# LCD_touch_conn.net
KiCad netlist of a schematic drawn in Altium Designer
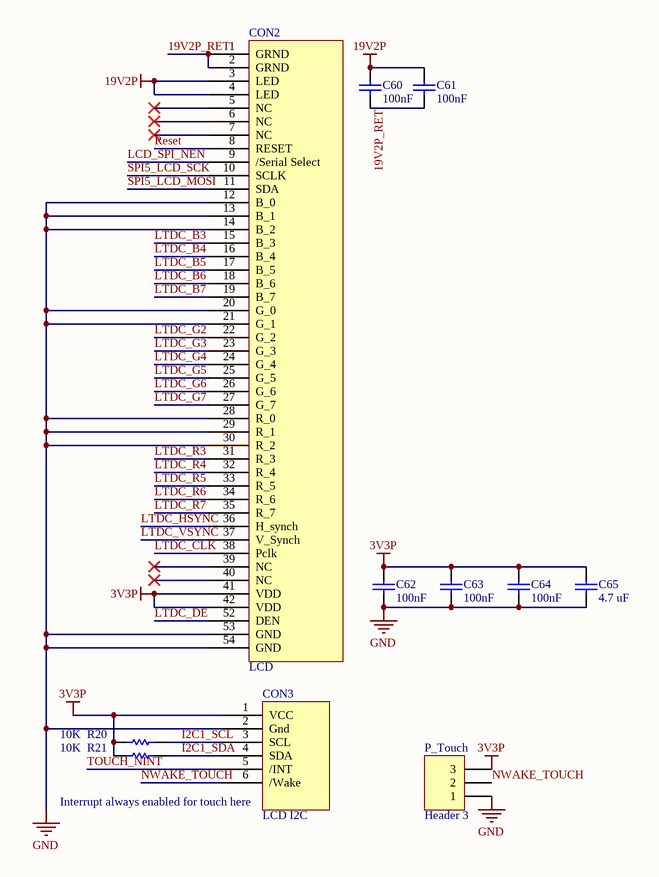
[diagram p0: LCD_touch_conn.SchDoc]

(export (version "E")
  (design (tool "Eeschema 10.0.6"))
  (components
    (comp (ref "C60")
      (value "100nF")
      (footprint "C0805")
      (description "Capacitor")
      (fields (field (name "PUBLISHER") "Altium Limited"))
      (libsource (lib "Miscellaneous Devices") (part "Cap"))
    )
    (comp (ref "C61")
      (value "100nF")
      (footprint "C0805")
      (description "Capacitor")
      (fields (field (name "PUBLISHER") "Altium Limited"))
      (libsource (lib "Miscellaneous Devices") (part "Cap"))
    )
    (comp (ref "C62")
      (value "100nF")
      (footprint "C0805")
      (description "Capacitor")
      (fields (field (name "PUBLISHER") "Altium Limited"))
      (libsource (lib "Miscellaneous Devices") (part "Cap"))
    )
    (comp (ref "C63")
      (value "100nF")
      (footprint "C0805")
      (description "Capacitor")
      (fields (field (name "PUBLISHER") "Altium Limited"))
      (libsource (lib "Miscellaneous Devices") (part "Cap"))
    )
    (comp (ref "C64")
      (value "100nF")
      (footprint "C0805")
      (description "Capacitor")
      (fields (field (name "PUBLISHER") "Altium Limited"))
      (libsource (lib "Miscellaneous Devices") (part "Cap"))
    )
    (comp (ref "C65")
      (value "4.7 uF")
      (footprint "C0805")
      (description "Capacitor")
      (fields (field (name "PUBLISHER") "Altium Limited"))
      (libsource (lib "Miscellaneous Devices") (part "Cap"))
    )
    (comp (ref "CON2")
      (value "LCD")
      (footprint "Molex54 - duplicate2")
      (libsource (lib "GameMan") (part "LCD"))
    )
    (comp (ref "CON3") (value "LCD I2C") (footprint "Molex6") (libsource (lib "GameMan") (part "LCD I2C")))
    (comp (ref "P_Touch")
      (value "Header 3")
      (footprint "HDR1X3")
      (description "Header, 3-Pin")
      (fields (field (name "PUBLISHER") "Altium Limited"))
      (libsource (lib "Miscellaneous Connectors") (part "Header 3"))
    )
    (comp (ref "R20")
      (value "10K")
      (footprint "6-0805_M")
      (description "Resistor")
      (fields (field (name "PUBLISHER") "Altium Limited"))
      (libsource (lib "Miscellaneous Devices") (part "Res1"))
    )
    (comp (ref "R21")
      (value "10K")
      (footprint "6-0805_M")
      (description "Resistor")
      (fields (field (name "PUBLISHER") "Altium Limited"))
      (libsource (lib "Miscellaneous Devices") (part "Res1"))
    )
  )
  (nets
    (net (code "1") (name "/19V2P_RET") (class "Default")
      (node (ref "C60") (pin "1") (pinfunction "1_1") (pintype "passive"))
      (node (ref "C61") (pin "1") (pinfunction "1_1") (pintype "passive"))
      (node (ref "CON2") (pin "1") (pinfunction "GRND_1") (pintype "passive"))
      (node (ref "CON2") (pin "2") (pinfunction "GRND_2") (pintype "passive"))
    )
    (net (code "2") (name "/I2C1_SCL") (class "Default")
      (node (ref "CON3") (pin "3") (pinfunction "SCL_3") (pintype "passive"))
      (node (ref "R20") (pin "2") (pinfunction "2_2") (pintype "passive"))
    )
    (net (code "3") (name "/I2C1_SDA") (class "Default")
      (node (ref "CON3") (pin "4") (pinfunction "SDA_4") (pintype "passive"))
      (node (ref "R21") (pin "2") (pinfunction "2_2") (pintype "passive"))
    )
    (net (code "4") (name "/LCD_SPI_NEN") (class "Default")
      (node (ref "CON2") (pin "9") (pinfunction "/Serial_Select_9") (pintype "passive"))
    )
    (net (code "5") (name "/LTDC_B3") (class "Default")
      (node (ref "CON2") (pin "15") (pinfunction "B_3_15") (pintype "passive"))
    )
    (net (code "6") (name "/LTDC_B4") (class "Default")
      (node (ref "CON2") (pin "16") (pinfunction "B_4_16") (pintype "passive"))
    )
    (net (code "7") (name "/LTDC_B5") (class "Default")
      (node (ref "CON2") (pin "17") (pinfunction "B_5_17") (pintype "passive"))
    )
    (net (code "8") (name "/LTDC_B6") (class "Default")
      (node (ref "CON2") (pin "18") (pinfunction "B_6_18") (pintype "passive"))
    )
    (net (code "9") (name "/LTDC_B7") (class "Default")
      (node (ref "CON2") (pin "19") (pinfunction "B_7_19") (pintype "passive"))
    )
    (net (code "10") (name "/LTDC_CLK") (class "Default")
      (node (ref "CON2") (pin "38") (pinfunction "Pclk_38") (pintype "passive"))
    )
    (net (code "11") (name "/LTDC_DE") (class "Default")
      (node (ref "CON2") (pin "52") (pinfunction "DEN_52") (pintype "passive"))
    )
    (net (code "12") (name "/LTDC_G2") (class "Default")
      (node (ref "CON2") (pin "22") (pinfunction "G_2_22") (pintype "passive"))
    )
    (net (code "13") (name "/LTDC_G3") (class "Default")
      (node (ref "CON2") (pin "23") (pinfunction "G_3_23") (pintype "passive"))
    )
    (net (code "14") (name "/LTDC_G4") (class "Default")
      (node (ref "CON2") (pin "24") (pinfunction "G_4_24") (pintype "passive"))
    )
    (net (code "15") (name "/LTDC_G5") (class "Default")
      (node (ref "CON2") (pin "25") (pinfunction "G_5_25") (pintype "passive"))
    )
    (net (code "16") (name "/LTDC_G6") (class "Default")
      (node (ref "CON2") (pin "26") (pinfunction "G_6_26") (pintype "passive"))
    )
    (net (code "17") (name "/LTDC_G7") (class "Default")
      (node (ref "CON2") (pin "27") (pinfunction "G_7_27") (pintype "passive"))
    )
    (net (code "18") (name "/LTDC_HSYNC") (class "Default")
      (node (ref "CON2") (pin "36") (pinfunction "H_synch_36") (pintype "passive"))
    )
    (net (code "19") (name "/LTDC_R3") (class "Default")
      (node (ref "CON2") (pin "31") (pinfunction "R_3_31") (pintype "passive"))
    )
    (net (code "20") (name "/LTDC_R4") (class "Default")
      (node (ref "CON2") (pin "32") (pinfunction "R_4_32") (pintype "passive"))
    )
    (net (code "21") (name "/LTDC_R5") (class "Default")
      (node (ref "CON2") (pin "33") (pinfunction "R_5_33") (pintype "passive"))
    )
    (net (code "22") (name "/LTDC_R6") (class "Default")
      (node (ref "CON2") (pin "34") (pinfunction "R_6_34") (pintype "passive"))
    )
    (net (code "23") (name "/LTDC_R7") (class "Default")
      (node (ref "CON2") (pin "35") (pinfunction "R_7_35") (pintype "passive"))
    )
    (net (code "24") (name "/LTDC_VSYNC") (class "Default")
      (node (ref "CON2") (pin "37") (pinfunction "V_Synch_37") (pintype "passive"))
    )
    (net (code "25") (name "/NWAKE_TOUCH") (class "Default")
      (node (ref "CON3") (pin "6") (pinfunction "/Wake_6") (pintype "passive"))
      (node (ref "P_Touch") (pin "2") (pinfunction "2_2") (pintype "passive"))
    )
    (net (code "26") (name "/Reset") (class "Default")
      (node (ref "CON2") (pin "8") (pinfunction "RESET_8") (pintype "passive"))
    )
    (net (code "27") (name "/SPI5_LCD_MOSI") (class "Default")
      (node (ref "CON2") (pin "11") (pinfunction "SDA_11") (pintype "passive"))
    )
    (net (code "28") (name "/SPI5_LCD_SCK") (class "Default")
      (node (ref "CON2") (pin "10") (pinfunction "SCLK_10") (pintype "passive"))
    )
    (net (code "29") (name "/TOUCH_NINT") (class "Default")
      (node (ref "CON3") (pin "5") (pinfunction "/INT_5") (pintype "passive"))
    )
    (net (code "30") (name "3V3P") (class "Default")
      (node (ref "C62") (pin "2") (pinfunction "2_2") (pintype "passive"))
      (node (ref "C63") (pin "2") (pinfunction "2_2") (pintype "passive"))
      (node (ref "C64") (pin "2") (pinfunction "2_2") (pintype "passive"))
      (node (ref "C65") (pin "2") (pinfunction "2_2") (pintype "passive"))
      (node (ref "CON2") (pin "41") (pinfunction "VDD_41") (pintype "passive"))
      (node (ref "CON2") (pin "42") (pinfunction "VDD_42") (pintype "passive"))
      (node (ref "CON3") (pin "1") (pinfunction "VCC_1") (pintype "passive"))
      (node (ref "P_Touch") (pin "3") (pinfunction "3_3") (pintype "passive"))
      (node (ref "R20") (pin "1") (pinfunction "1_1") (pintype "passive"))
      (node (ref "R21") (pin "1") (pinfunction "1_1") (pintype "passive"))
    )
    (net (code "31") (name "19V2P") (class "Default")
      (node (ref "C60") (pin "2") (pinfunction "2_2") (pintype "passive"))
      (node (ref "C61") (pin "2") (pinfunction "2_2") (pintype "passive"))
      (node (ref "CON2") (pin "3") (pinfunction "LED_3") (pintype "passive"))
      (node (ref "CON2") (pin "4") (pinfunction "LED_4") (pintype "passive"))
    )
    (net (code "32") (name "GND") (class "Default")
      (node (ref "C62") (pin "1") (pinfunction "1_1") (pintype "passive"))
      (node (ref "C63") (pin "1") (pinfunction "1_1") (pintype "passive"))
      (node (ref "C64") (pin "1") (pinfunction "1_1") (pintype "passive"))
      (node (ref "C65") (pin "1") (pinfunction "1_1") (pintype "passive"))
      (node (ref "CON2") (pin "12") (pinfunction "B_0_12") (pintype "passive"))
      (node (ref "CON2") (pin "13") (pinfunction "B_1_13") (pintype "passive"))
      (node (ref "CON2") (pin "14") (pinfunction "B_2_14") (pintype "passive"))
      (node (ref "CON2") (pin "20") (pinfunction "G_0_20") (pintype "passive"))
      (node (ref "CON2") (pin "21") (pinfunction "G_1_21") (pintype "passive"))
      (node (ref "CON2") (pin "28") (pinfunction "R_0_28") (pintype "passive"))
      (node (ref "CON2") (pin "29") (pinfunction "R_1_29") (pintype "passive"))
      (node (ref "CON2") (pin "30") (pinfunction "R_2_30") (pintype "passive"))
      (node (ref "CON2") (pin "53") (pinfunction "GND_53") (pintype "passive"))
      (node (ref "CON2") (pin "54") (pinfunction "GND_54") (pintype "passive"))
      (node (ref "CON3") (pin "2") (pinfunction "Gnd_2") (pintype "passive"))
      (node (ref "P_Touch") (pin "1") (pinfunction "1_1") (pintype "passive"))
    )
    (net (code "33") (name "unconnected-(CON2-NC-Pad5)") (class "Default")
      (node (ref "CON2") (pin "5") (pinfunction "NC_5") (pintype "passive+no_connect"))
    )
    (net (code "34") (name "unconnected-(CON2-NC-Pad6)") (class "Default")
      (node (ref "CON2") (pin "6") (pinfunction "NC_6") (pintype "passive+no_connect"))
    )
    (net (code "35") (name "unconnected-(CON2-NC-Pad7)") (class "Default")
      (node (ref "CON2") (pin "7") (pinfunction "NC_7") (pintype "passive+no_connect"))
    )
    (net (code "36") (name "unconnected-(CON2-NC-Pad39)") (class "Default")
      (node (ref "CON2") (pin "39") (pinfunction "NC_39") (pintype "passive+no_connect"))
    )
    (net (code "37") (name "unconnected-(CON2-NC-Pad40)") (class "Default")
      (node (ref "CON2") (pin "40") (pinfunction "NC_40") (pintype "passive+no_connect"))
    )
  )
)
